# SensorsTeam5.net
KiCad netlist of a schematic drawn in Altium Designer
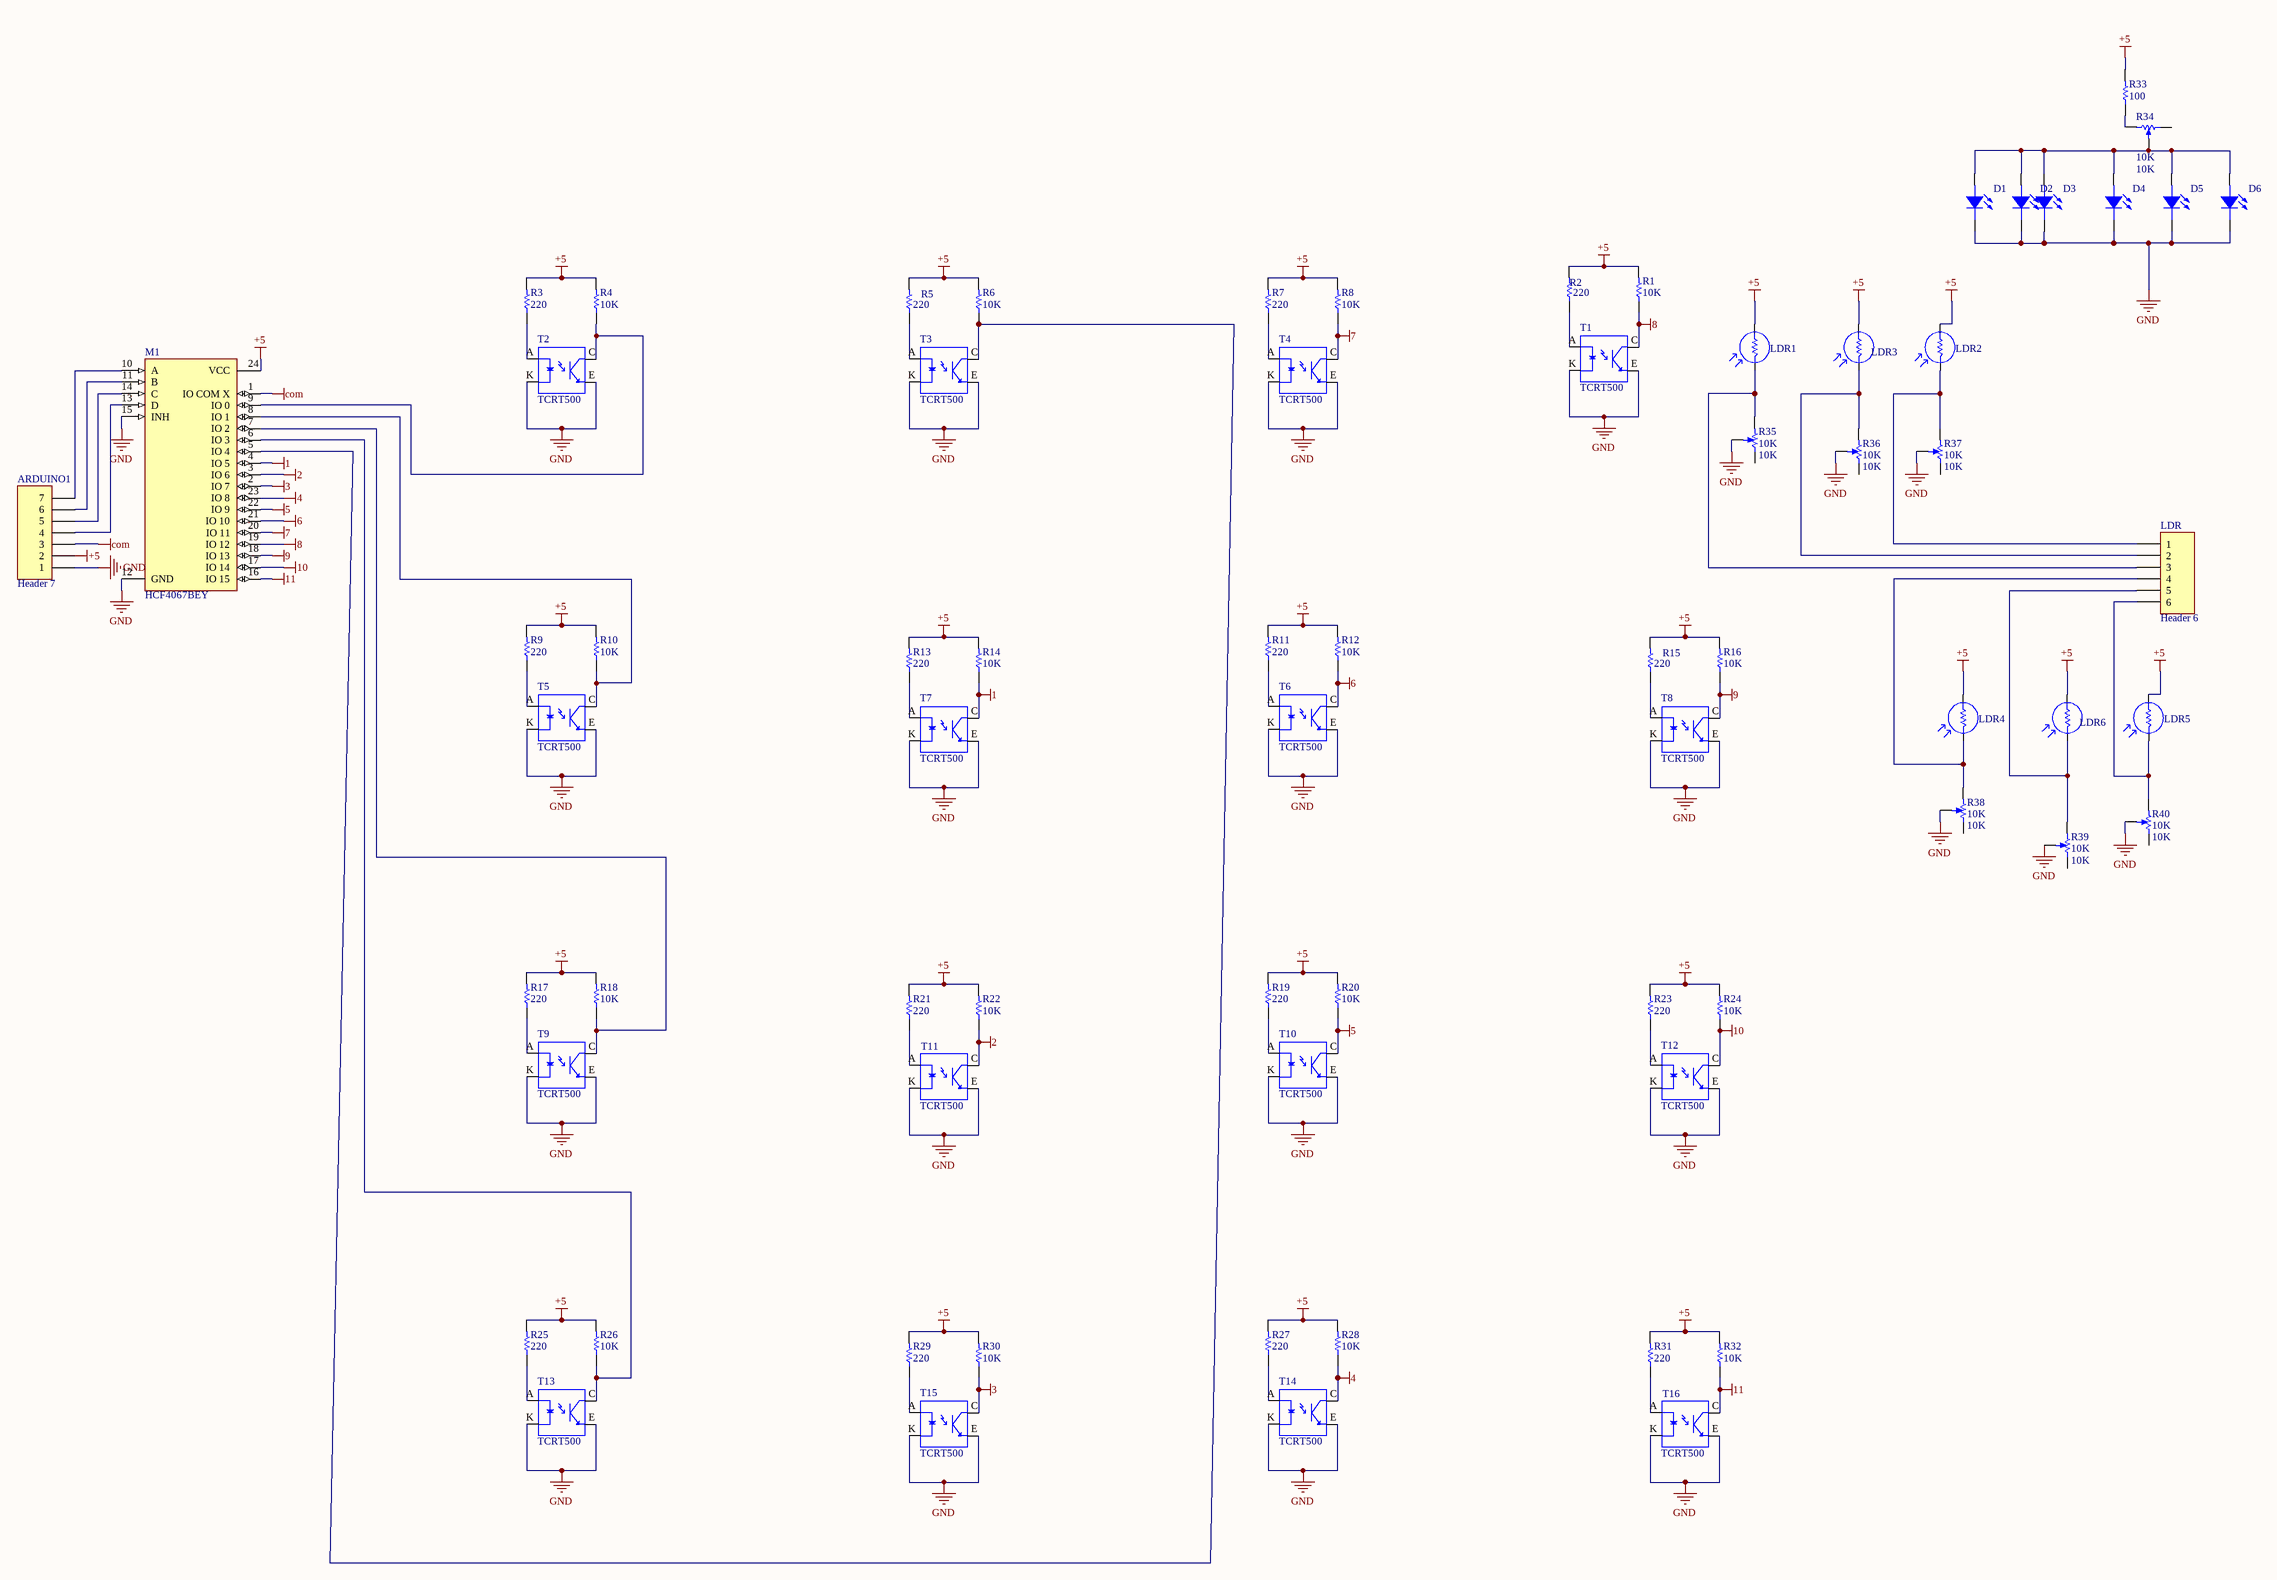
[diagram p0: SensorsTeam5.SchDoc]

(export (version "E")
  (design (tool "Eeschema 10.0.6"))
  (components
    (comp (ref "ARDUINO1")
      (value "Header 7")
      (footprint "HDR1X7")
      (description "Header, 7-Pin")
      (fields (field (name "PUBLISHER") "Altium Limited"))
      (libsource (lib "Altium") (part "Header 7"))
    )
    (comp (ref "D1")
      (value "LED3MM")
      (footprint "LED3mm_GRN")
      (description "Light Emitting Diode")
      (fields (field (name "DESIGNER") "Ali Hafizi"))
      (libsource (lib "Altium") (part "LED 3MM"))
    )
    (comp (ref "D2")
      (value "LED3MM")
      (footprint "LED3mm_GRN")
      (description "Light Emitting Diode")
      (fields (field (name "DESIGNER") "Ali Hafizi"))
      (libsource (lib "Altium") (part "LED 3MM"))
    )
    (comp (ref "D3")
      (value "LED3MM")
      (footprint "LED3mm_GRN")
      (description "Light Emitting Diode")
      (fields (field (name "DESIGNER") "Ali Hafizi"))
      (libsource (lib "Altium") (part "LED 3MM"))
    )
    (comp (ref "D4")
      (value "LED3MM")
      (footprint "LED3mm_GRN")
      (description "Light Emitting Diode")
      (fields (field (name "DESIGNER") "Ali Hafizi"))
      (libsource (lib "Altium") (part "LED 3MM"))
    )
    (comp (ref "D5")
      (value "LED3MM")
      (footprint "LED3mm_GRN")
      (description "Light Emitting Diode")
      (fields (field (name "DESIGNER") "Ali Hafizi"))
      (libsource (lib "Altium") (part "LED 3MM"))
    )
    (comp (ref "D6")
      (value "LED3MM")
      (footprint "LED3mm_GRN")
      (description "Light Emitting Diode")
      (fields (field (name "DESIGNER") "Ali Hafizi"))
      (libsource (lib "Altium") (part "LED 3MM"))
    )
    (comp (ref "LDR")
      (value "Header 6")
      (footprint "HDR1X6")
      (description "Header, 6-Pin")
      (fields (field (name "PUBLISHER") "Altium Limited"))
      (libsource (lib "Altium") (part "Header 6"))
    )
    (comp (ref "LDR1")
      (value "PhotoCell")
      (footprint "PhotoCell")
      (description "Photo Cell- Variable Resistor With Light")
      (fields (field (name "DESIGNER") "Saeid Jorablo"))
      (libsource (lib "Altium") (part "LDR"))
    )
    (comp (ref "LDR2")
      (value "PhotoCell")
      (footprint "PhotoCell")
      (description "Photo Cell- Variable Resistor With Light")
      (fields (field (name "DESIGNER") "Saeid Jorablo"))
      (libsource (lib "Altium") (part "LDR"))
    )
    (comp (ref "LDR3")
      (value "PhotoCell")
      (footprint "PhotoCell")
      (description "Photo Cell- Variable Resistor With Light")
      (fields (field (name "DESIGNER") "Saeid Jorablo"))
      (libsource (lib "Altium") (part "LDR"))
    )
    (comp (ref "LDR4")
      (value "PhotoCell")
      (footprint "PhotoCell")
      (description "Photo Cell- Variable Resistor With Light")
      (fields (field (name "DESIGNER") "Saeid Jorablo"))
      (libsource (lib "Altium") (part "LDR"))
    )
    (comp (ref "LDR5")
      (value "PhotoCell")
      (footprint "PhotoCell")
      (description "Photo Cell- Variable Resistor With Light")
      (fields (field (name "DESIGNER") "Saeid Jorablo"))
      (libsource (lib "Altium") (part "LDR"))
    )
    (comp (ref "LDR6")
      (value "PhotoCell")
      (footprint "PhotoCell")
      (description "Photo Cell- Variable Resistor With Light")
      (fields (field (name "DESIGNER") "Saeid Jorablo"))
      (libsource (lib "Altium") (part "LDR"))
    )
    (comp (ref "M1")
      (value "HCF4067BEY")
      (footprint "PDIP24")
      (description "Analog Multiplexer/Demultiplexer")
      (fields (field (name "PUBLISHER") "Altium Limited"))
      (libsource (lib "ST Logic Multiplexer") (part "HCF4067BEY"))
    )
    (comp (ref "R1")
      (value "10K")
      (footprint "RES-(1/4)")
      (description "RES 0805")
      (fields (field (name "DESIGNER") "Abbas Basereh"))
      (libsource (lib "Altium") (part "RES 0805 0.125W"))
    )
    (comp (ref "R2")
      (value "220")
      (footprint "RES-(1/4)")
      (description "RES 0805")
      (fields (field (name "DESIGNER") "Abbas Basereh"))
      (libsource (lib "Altium") (part "RES 0805 0.125W"))
    )
    (comp (ref "R3")
      (value "220")
      (footprint "RES-(1/4)")
      (description "RES 0805")
      (fields (field (name "DESIGNER") "Abbas Basereh"))
      (libsource (lib "Altium") (part "RES 0805 0.125W"))
    )
    (comp (ref "R4")
      (value "10K")
      (footprint "RES-(1/4)")
      (description "RES 0805")
      (fields (field (name "DESIGNER") "Abbas Basereh"))
      (libsource (lib "Altium") (part "RES 0805 0.125W"))
    )
    (comp (ref "R5")
      (value "220")
      (footprint "RES-(1/4)")
      (description "RES 0805")
      (fields (field (name "DESIGNER") "Abbas Basereh"))
      (libsource (lib "Altium") (part "RES 0805 0.125W"))
    )
    (comp (ref "R6")
      (value "10K")
      (footprint "RES-(1/4)")
      (description "RES 0805")
      (fields (field (name "DESIGNER") "Abbas Basereh"))
      (libsource (lib "Altium") (part "RES 0805 0.125W"))
    )
    (comp (ref "R7")
      (value "220")
      (footprint "RES-(1/4)")
      (description "RES 0805")
      (fields (field (name "DESIGNER") "Abbas Basereh"))
      (libsource (lib "Altium") (part "RES 0805 0.125W"))
    )
    (comp (ref "R8")
      (value "10K")
      (footprint "RES-(1/4)")
      (description "RES 0805")
      (fields (field (name "DESIGNER") "Abbas Basereh"))
      (libsource (lib "Altium") (part "RES 0805 0.125W"))
    )
    (comp (ref "R9")
      (value "220")
      (footprint "RES-(1/4)")
      (description "RES 0805")
      (fields (field (name "DESIGNER") "Abbas Basereh"))
      (libsource (lib "Altium") (part "RES 0805 0.125W"))
    )
    (comp (ref "R10")
      (value "10K")
      (footprint "RES-(1/4)")
      (description "RES 0805")
      (fields (field (name "DESIGNER") "Abbas Basereh"))
      (libsource (lib "Altium") (part "RES 0805 0.125W"))
    )
    (comp (ref "R11")
      (value "220")
      (footprint "RES-(1/4)")
      (description "RES 0805")
      (fields (field (name "DESIGNER") "Abbas Basereh"))
      (libsource (lib "Altium") (part "RES 0805 0.125W"))
    )
    (comp (ref "R12")
      (value "10K")
      (footprint "RES-(1/4)")
      (description "RES 0805")
      (fields (field (name "DESIGNER") "Abbas Basereh"))
      (libsource (lib "Altium") (part "RES 0805 0.125W"))
    )
    (comp (ref "R13")
      (value "220")
      (footprint "RES-(1/4)")
      (description "RES 0805")
      (fields (field (name "DESIGNER") "Abbas Basereh"))
      (libsource (lib "Altium") (part "RES 0805 0.125W"))
    )
    (comp (ref "R14")
      (value "10K")
      (footprint "RES-(1/4)")
      (description "RES 0805")
      (fields (field (name "DESIGNER") "Abbas Basereh"))
      (libsource (lib "Altium") (part "RES 0805 0.125W"))
    )
    (comp (ref "R15")
      (value "220")
      (footprint "RES-(1/4)")
      (description "RES 0805")
      (fields (field (name "DESIGNER") "Abbas Basereh"))
      (libsource (lib "Altium") (part "RES 0805 0.125W"))
    )
    (comp (ref "R16")
      (value "10K")
      (footprint "RES-(1/4)")
      (description "RES 0805")
      (fields (field (name "DESIGNER") "Abbas Basereh"))
      (libsource (lib "Altium") (part "RES 0805 0.125W"))
    )
    (comp (ref "R17")
      (value "220")
      (footprint "RES-(1/4)")
      (description "RES 0805")
      (fields (field (name "DESIGNER") "Abbas Basereh"))
      (libsource (lib "Altium") (part "RES 0805 0.125W"))
    )
    (comp (ref "R18")
      (value "10K")
      (footprint "RES-(1/4)")
      (description "RES 0805")
      (fields (field (name "DESIGNER") "Abbas Basereh"))
      (libsource (lib "Altium") (part "RES 0805 0.125W"))
    )
    (comp (ref "R19")
      (value "220")
      (footprint "RES-(1/4)")
      (description "RES 0805")
      (fields (field (name "DESIGNER") "Abbas Basereh"))
      (libsource (lib "Altium") (part "RES 0805 0.125W"))
    )
    (comp (ref "R20")
      (value "10K")
      (footprint "RES-(1/4)")
      (description "RES 0805")
      (fields (field (name "DESIGNER") "Abbas Basereh"))
      (libsource (lib "Altium") (part "RES 0805 0.125W"))
    )
    (comp (ref "R21")
      (value "220")
      (footprint "RES-(1/4)")
      (description "RES 0805")
      (fields (field (name "DESIGNER") "Abbas Basereh"))
      (libsource (lib "Altium") (part "RES 0805 0.125W"))
    )
    (comp (ref "R22")
      (value "10K")
      (footprint "RES-(1/4)")
      (description "RES 0805")
      (fields (field (name "DESIGNER") "Abbas Basereh"))
      (libsource (lib "Altium") (part "RES 0805 0.125W"))
    )
    (comp (ref "R23")
      (value "220")
      (footprint "RES-(1/4)")
      (description "RES 0805")
      (fields (field (name "DESIGNER") "Abbas Basereh"))
      (libsource (lib "Altium") (part "RES 0805 0.125W"))
    )
    (comp (ref "R24")
      (value "10K")
      (footprint "RES-(1/4)")
      (description "RES 0805")
      (fields (field (name "DESIGNER") "Abbas Basereh"))
      (libsource (lib "Altium") (part "RES 0805 0.125W"))
    )
    (comp (ref "R25")
      (value "220")
      (footprint "RES-(1/4)")
      (description "RES 0805")
      (fields (field (name "DESIGNER") "Abbas Basereh"))
      (libsource (lib "Altium") (part "RES 0805 0.125W"))
    )
    (comp (ref "R26")
      (value "10K")
      (footprint "RES-(1/4)")
      (description "RES 0805")
      (fields (field (name "DESIGNER") "Abbas Basereh"))
      (libsource (lib "Altium") (part "RES 0805 0.125W"))
    )
    (comp (ref "R27")
      (value "220")
      (footprint "RES-(1/4)")
      (description "RES 0805")
      (fields (field (name "DESIGNER") "Abbas Basereh"))
      (libsource (lib "Altium") (part "RES 0805 0.125W"))
    )
    (comp (ref "R28")
      (value "10K")
      (footprint "RES-(1/4)")
      (description "RES 0805")
      (fields (field (name "DESIGNER") "Abbas Basereh"))
      (libsource (lib "Altium") (part "RES 0805 0.125W"))
    )
    (comp (ref "R29")
      (value "220")
      (footprint "RES-(1/4)")
      (description "RES 0805")
      (fields (field (name "DESIGNER") "Abbas Basereh"))
      (libsource (lib "Altium") (part "RES 0805 0.125W"))
    )
    (comp (ref "R30")
      (value "10K")
      (footprint "RES-(1/4)")
      (description "RES 0805")
      (fields (field (name "DESIGNER") "Abbas Basereh"))
      (libsource (lib "Altium") (part "RES 0805 0.125W"))
    )
    (comp (ref "R31")
      (value "220")
      (footprint "RES-(1/4)")
      (description "RES 0805")
      (fields (field (name "DESIGNER") "Abbas Basereh"))
      (libsource (lib "Altium") (part "RES 0805 0.125W"))
    )
    (comp (ref "R32")
      (value "10K")
      (footprint "RES-(1/4)")
      (description "RES 0805")
      (fields (field (name "DESIGNER") "Abbas Basereh"))
      (libsource (lib "Altium") (part "RES 0805 0.125W"))
    )
    (comp (ref "R33")
      (value "100")
      (footprint "RESC3413X04N")
      (description "RES 0805")
      (fields (field (name "DESIGNER") "Abbas Basereh"))
      (libsource (lib "Altium") (part "RES 0805 0.125W"))
    )
    (comp (ref "R34")
      (value "10K")
      (footprint "POT4MM-Small Pot")
      (description "Square Trimming Potentiometer")
      (fields (field (name "ALTIUM_VALUE") "10K") (field (name "PUBLISHER") "Altium Limited"))
      (libsource (lib "Altium") (part "POT SMD"))
    )
    (comp (ref "R35")
      (value "10K")
      (footprint "POT4MM-Small Pot")
      (description "Square Trimming Potentiometer")
      (fields (field (name "ALTIUM_VALUE") "10K") (field (name "PUBLISHER") "Altium Limited"))
      (libsource (lib "Altium") (part "POT SMD"))
    )
    (comp (ref "R36")
      (value "10K")
      (footprint "POT4MM-Small Pot")
      (description "Square Trimming Potentiometer")
      (fields (field (name "ALTIUM_VALUE") "10K") (field (name "PUBLISHER") "Altium Limited"))
      (libsource (lib "Altium") (part "POT SMD"))
    )
    (comp (ref "R37")
      (value "10K")
      (footprint "POT4MM-Small Pot")
      (description "Square Trimming Potentiometer")
      (fields (field (name "ALTIUM_VALUE") "10K") (field (name "PUBLISHER") "Altium Limited"))
      (libsource (lib "Altium") (part "POT SMD"))
    )
    (comp (ref "R38")
      (value "10K")
      (footprint "POT4MM-Small Pot")
      (description "Square Trimming Potentiometer")
      (fields (field (name "ALTIUM_VALUE") "10K") (field (name "PUBLISHER") "Altium Limited"))
      (libsource (lib "Altium") (part "POT SMD"))
    )
    (comp (ref "R39")
      (value "10K")
      (footprint "POT4MM-Small Pot")
      (description "Square Trimming Potentiometer")
      (fields (field (name "ALTIUM_VALUE") "10K") (field (name "PUBLISHER") "Altium Limited"))
      (libsource (lib "Altium") (part "POT SMD"))
    )
    (comp (ref "R40")
      (value "10K")
      (footprint "POT4MM-Small Pot")
      (description "Square Trimming Potentiometer")
      (fields (field (name "ALTIUM_VALUE") "10K") (field (name "PUBLISHER") "Altium Limited"))
      (libsource (lib "Altium") (part "POT SMD"))
    )
    (comp (ref "T1") (value "TCRT500") (footprint "TCRT5000") (libsource (lib "Mahmah") (part "TCRT5000")))
    (comp (ref "T2") (value "TCRT500") (footprint "TCRT5000") (libsource (lib "Mahmah") (part "TCRT5000")))
    (comp (ref "T3") (value "TCRT500") (footprint "TCRT5000") (libsource (lib "Mahmah") (part "TCRT5000")))
    (comp (ref "T4") (value "TCRT500") (footprint "TCRT5000") (libsource (lib "Mahmah") (part "TCRT5000")))
    (comp (ref "T5") (value "TCRT500") (footprint "TCRT5000") (libsource (lib "Mahmah") (part "TCRT5000")))
    (comp (ref "T6") (value "TCRT500") (footprint "TCRT5000") (libsource (lib "Mahmah") (part "TCRT5000")))
    (comp (ref "T7") (value "TCRT500") (footprint "TCRT5000") (libsource (lib "Mahmah") (part "TCRT5000")))
    (comp (ref "T8") (value "TCRT500") (footprint "TCRT5000") (libsource (lib "Mahmah") (part "TCRT5000")))
    (comp (ref "T9") (value "TCRT500") (footprint "TCRT5000") (libsource (lib "Mahmah") (part "TCRT5000")))
    (comp (ref "T10") (value "TCRT500") (footprint "TCRT5000") (libsource (lib "Mahmah") (part "TCRT5000")))
    (comp (ref "T11") (value "TCRT500") (footprint "TCRT5000") (libsource (lib "Mahmah") (part "TCRT5000")))
    (comp (ref "T12") (value "TCRT500") (footprint "TCRT5000") (libsource (lib "Mahmah") (part "TCRT5000")))
    (comp (ref "T13") (value "TCRT500") (footprint "TCRT5000") (libsource (lib "Mahmah") (part "TCRT5000")))
    (comp (ref "T14") (value "TCRT500") (footprint "TCRT5000") (libsource (lib "Mahmah") (part "TCRT5000")))
    (comp (ref "T15") (value "TCRT500") (footprint "TCRT5000") (libsource (lib "Mahmah") (part "TCRT5000")))
    (comp (ref "T16") (value "TCRT500") (footprint "TCRT5000") (libsource (lib "Mahmah") (part "TCRT5000")))
  )
  (nets
    (net (code "1") (name "+5") (class "Default")
      (node (ref "ARDUINO1") (pin "2") (pinfunction "2_2") (pintype "passive"))
      (node (ref "LDR1") (pin "2") (pintype "passive"))
      (node (ref "LDR2") (pin "2") (pintype "passive"))
      (node (ref "LDR3") (pin "2") (pintype "passive"))
      (node (ref "LDR4") (pin "2") (pintype "passive"))
      (node (ref "LDR5") (pin "2") (pintype "passive"))
      (node (ref "LDR6") (pin "2") (pintype "passive"))
      (node (ref "M1") (pin "24") (pinfunction "VCC_24") (pintype "power_in"))
      (node (ref "R1") (pin "2") (pinfunction "2_2") (pintype "passive"))
      (node (ref "R10") (pin "2") (pinfunction "2_2") (pintype "passive"))
      (node (ref "R11") (pin "2") (pinfunction "2_2") (pintype "passive"))
      (node (ref "R12") (pin "2") (pinfunction "2_2") (pintype "passive"))
      (node (ref "R13") (pin "2") (pinfunction "2_2") (pintype "passive"))
      (node (ref "R14") (pin "2") (pinfunction "2_2") (pintype "passive"))
      (node (ref "R15") (pin "2") (pinfunction "2_2") (pintype "passive"))
      (node (ref "R16") (pin "2") (pinfunction "2_2") (pintype "passive"))
      (node (ref "R17") (pin "2") (pinfunction "2_2") (pintype "passive"))
      (node (ref "R18") (pin "2") (pinfunction "2_2") (pintype "passive"))
      (node (ref "R19") (pin "2") (pinfunction "2_2") (pintype "passive"))
      (node (ref "R2") (pin "2") (pinfunction "2_2") (pintype "passive"))
      (node (ref "R20") (pin "2") (pinfunction "2_2") (pintype "passive"))
      (node (ref "R21") (pin "2") (pinfunction "2_2") (pintype "passive"))
      (node (ref "R22") (pin "2") (pinfunction "2_2") (pintype "passive"))
      (node (ref "R23") (pin "2") (pinfunction "2_2") (pintype "passive"))
      (node (ref "R24") (pin "2") (pinfunction "2_2") (pintype "passive"))
      (node (ref "R25") (pin "2") (pinfunction "2_2") (pintype "passive"))
      (node (ref "R26") (pin "2") (pinfunction "2_2") (pintype "passive"))
      (node (ref "R27") (pin "2") (pinfunction "2_2") (pintype "passive"))
      (node (ref "R28") (pin "2") (pinfunction "2_2") (pintype "passive"))
      (node (ref "R29") (pin "2") (pinfunction "2_2") (pintype "passive"))
      (node (ref "R3") (pin "2") (pinfunction "2_2") (pintype "passive"))
      (node (ref "R30") (pin "2") (pinfunction "2_2") (pintype "passive"))
      (node (ref "R31") (pin "2") (pinfunction "2_2") (pintype "passive"))
      (node (ref "R32") (pin "2") (pinfunction "2_2") (pintype "passive"))
      (node (ref "R33") (pin "2") (pinfunction "2_2") (pintype "passive"))
      (node (ref "R4") (pin "2") (pinfunction "2_2") (pintype "passive"))
      (node (ref "R5") (pin "2") (pinfunction "2_2") (pintype "passive"))
      (node (ref "R6") (pin "2") (pinfunction "2_2") (pintype "passive"))
      (node (ref "R7") (pin "2") (pinfunction "2_2") (pintype "passive"))
      (node (ref "R8") (pin "2") (pinfunction "2_2") (pintype "passive"))
      (node (ref "R9") (pin "2") (pinfunction "2_2") (pintype "passive"))
    )
    (net (code "2") (name "1") (class "Default")
      (node (ref "M1") (pin "4") (pinfunction "IO_5_4") (pintype "bidirectional"))
      (node (ref "R14") (pin "1") (pinfunction "1_1") (pintype "passive"))
      (node (ref "T7") (pin "C") (pinfunction "C_C") (pintype "passive"))
    )
    (net (code "3") (name "2") (class "Default")
      (node (ref "M1") (pin "3") (pinfunction "IO_6_3") (pintype "bidirectional"))
      (node (ref "R22") (pin "1") (pinfunction "1_1") (pintype "passive"))
      (node (ref "T11") (pin "C") (pinfunction "C_C") (pintype "passive"))
    )
    (net (code "4") (name "3") (class "Default")
      (node (ref "M1") (pin "2") (pinfunction "IO_7_2") (pintype "bidirectional"))
      (node (ref "R30") (pin "1") (pinfunction "1_1") (pintype "passive"))
      (node (ref "T15") (pin "C") (pinfunction "C_C") (pintype "passive"))
    )
    (net (code "5") (name "4") (class "Default")
      (node (ref "M1") (pin "23") (pinfunction "IO_8_23") (pintype "bidirectional"))
      (node (ref "R28") (pin "1") (pinfunction "1_1") (pintype "passive"))
      (node (ref "T14") (pin "C") (pinfunction "C_C") (pintype "passive"))
    )
    (net (code "6") (name "5") (class "Default")
      (node (ref "M1") (pin "22") (pinfunction "IO_9_22") (pintype "bidirectional"))
      (node (ref "R20") (pin "1") (pinfunction "1_1") (pintype "passive"))
      (node (ref "T10") (pin "C") (pinfunction "C_C") (pintype "passive"))
    )
    (net (code "7") (name "6") (class "Default")
      (node (ref "M1") (pin "21") (pinfunction "IO_10_21") (pintype "bidirectional"))
      (node (ref "R12") (pin "1") (pinfunction "1_1") (pintype "passive"))
      (node (ref "T6") (pin "C") (pinfunction "C_C") (pintype "passive"))
    )
    (net (code "8") (name "7") (class "Default")
      (node (ref "M1") (pin "20") (pinfunction "IO_11_20") (pintype "bidirectional"))
      (node (ref "R8") (pin "1") (pinfunction "1_1") (pintype "passive"))
      (node (ref "T4") (pin "C") (pinfunction "C_C") (pintype "passive"))
    )
    (net (code "9") (name "8") (class "Default")
      (node (ref "M1") (pin "19") (pinfunction "IO_12_19") (pintype "bidirectional"))
      (node (ref "R1") (pin "1") (pinfunction "1_1") (pintype "passive"))
      (node (ref "T1") (pin "C") (pinfunction "C_C") (pintype "passive"))
    )
    (net (code "10") (name "9") (class "Default")
      (node (ref "M1") (pin "18") (pinfunction "IO_13_18") (pintype "bidirectional"))
      (node (ref "R16") (pin "1") (pinfunction "1_1") (pintype "passive"))
      (node (ref "T8") (pin "C") (pinfunction "C_C") (pintype "passive"))
    )
    (net (code "11") (name "10") (class "Default")
      (node (ref "M1") (pin "17") (pinfunction "IO_14_17") (pintype "bidirectional"))
      (node (ref "R24") (pin "1") (pinfunction "1_1") (pintype "passive"))
      (node (ref "T12") (pin "C") (pinfunction "C_C") (pintype "passive"))
    )
    (net (code "12") (name "11") (class "Default")
      (node (ref "M1") (pin "16") (pinfunction "IO_15_16") (pintype "bidirectional"))
      (node (ref "R32") (pin "1") (pinfunction "1_1") (pintype "passive"))
      (node (ref "T16") (pin "C") (pinfunction "C_C") (pintype "passive"))
    )
    (net (code "13") (name "GND") (class "Default")
      (node (ref "ARDUINO1") (pin "1") (pinfunction "1_1") (pintype "passive"))
      (node (ref "D1") (pin "2") (pinfunction "CATHODE_2") (pintype "passive"))
      (node (ref "D2") (pin "2") (pinfunction "CATHODE_2") (pintype "passive"))
      (node (ref "D3") (pin "2") (pinfunction "CATHODE_2") (pintype "passive"))
      (node (ref "D4") (pin "2") (pinfunction "CATHODE_2") (pintype "passive"))
      (node (ref "D5") (pin "2") (pinfunction "CATHODE_2") (pintype "passive"))
      (node (ref "D6") (pin "2") (pinfunction "CATHODE_2") (pintype "passive"))
      (node (ref "M1") (pin "12") (pinfunction "GND_12") (pintype "power_in"))
      (node (ref "M1") (pin "15") (pinfunction "INH_15") (pintype "input"))
      (node (ref "R35") (pin "W") (pinfunction "W_W") (pintype "passive"))
      (node (ref "R36") (pin "W") (pinfunction "W_W") (pintype "passive"))
      (node (ref "R37") (pin "W") (pinfunction "W_W") (pintype "passive"))
      (node (ref "R38") (pin "W") (pinfunction "W_W") (pintype "passive"))
      (node (ref "R39") (pin "W") (pinfunction "W_W") (pintype "passive"))
      (node (ref "R40") (pin "W") (pinfunction "W_W") (pintype "passive"))
      (node (ref "T1") (pin "E") (pinfunction "E_E") (pintype "passive"))
      (node (ref "T1") (pin "K") (pinfunction "K_K") (pintype "passive"))
      (node (ref "T10") (pin "E") (pinfunction "E_E") (pintype "passive"))
      (node (ref "T10") (pin "K") (pinfunction "K_K") (pintype "passive"))
      (node (ref "T11") (pin "E") (pinfunction "E_E") (pintype "passive"))
      (node (ref "T11") (pin "K") (pinfunction "K_K") (pintype "passive"))
      (node (ref "T12") (pin "E") (pinfunction "E_E") (pintype "passive"))
      (node (ref "T12") (pin "K") (pinfunction "K_K") (pintype "passive"))
      (node (ref "T13") (pin "E") (pinfunction "E_E") (pintype "passive"))
      (node (ref "T13") (pin "K") (pinfunction "K_K") (pintype "passive"))
      (node (ref "T14") (pin "E") (pinfunction "E_E") (pintype "passive"))
      (node (ref "T14") (pin "K") (pinfunction "K_K") (pintype "passive"))
      (node (ref "T15") (pin "E") (pinfunction "E_E") (pintype "passive"))
      (node (ref "T15") (pin "K") (pinfunction "K_K") (pintype "passive"))
      (node (ref "T16") (pin "E") (pinfunction "E_E") (pintype "passive"))
      (node (ref "T16") (pin "K") (pinfunction "K_K") (pintype "passive"))
      (node (ref "T2") (pin "E") (pinfunction "E_E") (pintype "passive"))
      (node (ref "T2") (pin "K") (pinfunction "K_K") (pintype "passive"))
      (node (ref "T3") (pin "E") (pinfunction "E_E") (pintype "passive"))
      (node (ref "T3") (pin "K") (pinfunction "K_K") (pintype "passive"))
      (node (ref "T4") (pin "E") (pinfunction "E_E") (pintype "passive"))
      (node (ref "T4") (pin "K") (pinfunction "K_K") (pintype "passive"))
      (node (ref "T5") (pin "E") (pinfunction "E_E") (pintype "passive"))
      (node (ref "T5") (pin "K") (pinfunction "K_K") (pintype "passive"))
      (node (ref "T6") (pin "E") (pinfunction "E_E") (pintype "passive"))
      (node (ref "T6") (pin "K") (pinfunction "K_K") (pintype "passive"))
      (node (ref "T7") (pin "E") (pinfunction "E_E") (pintype "passive"))
      (node (ref "T7") (pin "K") (pinfunction "K_K") (pintype "passive"))
      (node (ref "T8") (pin "E") (pinfunction "E_E") (pintype "passive"))
      (node (ref "T8") (pin "K") (pinfunction "K_K") (pintype "passive"))
      (node (ref "T9") (pin "E") (pinfunction "E_E") (pintype "passive"))
      (node (ref "T9") (pin "K") (pinfunction "K_K") (pintype "passive"))
    )
    (net (code "14") (name "Net-(D1-ANODE)") (class "Default")
      (node (ref "D1") (pin "1") (pinfunction "ANODE_1") (pintype "passive"))
      (node (ref "D2") (pin "1") (pinfunction "ANODE_1") (pintype "passive"))
      (node (ref "D3") (pin "1") (pinfunction "ANODE_1") (pintype "passive"))
      (node (ref "D4") (pin "1") (pinfunction "ANODE_1") (pintype "passive"))
      (node (ref "D5") (pin "1") (pinfunction "ANODE_1") (pintype "passive"))
      (node (ref "D6") (pin "1") (pinfunction "ANODE_1") (pintype "passive"))
      (node (ref "R34") (pin "W") (pinfunction "W_W") (pintype "passive"))
    )
    (net (code "15") (name "Net-(M1-A)") (class "Default")
      (node (ref "ARDUINO1") (pin "7") (pinfunction "7_7") (pintype "passive"))
      (node (ref "M1") (pin "10") (pinfunction "A_10") (pintype "input"))
    )
    (net (code "16") (name "Net-(M1-B)") (class "Default")
      (node (ref "ARDUINO1") (pin "6") (pinfunction "6_6") (pintype "passive"))
      (node (ref "M1") (pin "11") (pinfunction "B_11") (pintype "input"))
    )
    (net (code "17") (name "Net-(M1-C)") (class "Default")
      (node (ref "ARDUINO1") (pin "5") (pinfunction "5_5") (pintype "passive"))
      (node (ref "M1") (pin "14") (pinfunction "C_14") (pintype "input"))
    )
    (net (code "18") (name "Net-(M1-D)") (class "Default")
      (node (ref "ARDUINO1") (pin "4") (pinfunction "4_4") (pintype "passive"))
      (node (ref "M1") (pin "13") (pinfunction "D_13") (pintype "input"))
    )
    (net (code "19") (name "Net-(M1-IO_0)") (class "Default")
      (node (ref "M1") (pin "9") (pinfunction "IO_0_9") (pintype "bidirectional"))
      (node (ref "R4") (pin "1") (pinfunction "1_1") (pintype "passive"))
      (node (ref "T2") (pin "C") (pinfunction "C_C") (pintype "passive"))
    )
    (net (code "20") (name "Net-(M1-IO_1)") (class "Default")
      (node (ref "M1") (pin "8") (pinfunction "IO_1_8") (pintype "bidirectional"))
      (node (ref "R10") (pin "1") (pinfunction "1_1") (pintype "passive"))
      (node (ref "T5") (pin "C") (pinfunction "C_C") (pintype "passive"))
    )
    (net (code "21") (name "Net-(M1-IO_2)") (class "Default")
      (node (ref "M1") (pin "7") (pinfunction "IO_2_7") (pintype "bidirectional"))
      (node (ref "R18") (pin "1") (pinfunction "1_1") (pintype "passive"))
      (node (ref "T9") (pin "C") (pinfunction "C_C") (pintype "passive"))
    )
    (net (code "22") (name "Net-(M1-IO_3)") (class "Default")
      (node (ref "M1") (pin "6") (pinfunction "IO_3_6") (pintype "bidirectional"))
      (node (ref "R26") (pin "1") (pinfunction "1_1") (pintype "passive"))
      (node (ref "T13") (pin "C") (pinfunction "C_C") (pintype "passive"))
    )
    (net (code "23") (name "Net-(M1-IO_4)") (class "Default")
      (node (ref "M1") (pin "5") (pinfunction "IO_4_5") (pintype "bidirectional"))
      (node (ref "R6") (pin "1") (pinfunction "1_1") (pintype "passive"))
      (node (ref "T3") (pin "C") (pinfunction "C_C") (pintype "passive"))
    )
    (net (code "24") (name "Net-(R2-Pad1)") (class "Default")
      (node (ref "R2") (pin "1") (pinfunction "1_1") (pintype "passive"))
      (node (ref "T1") (pin "A") (pinfunction "A_A") (pintype "passive"))
    )
    (net (code "25") (name "Net-(R3-Pad1)") (class "Default")
      (node (ref "R3") (pin "1") (pinfunction "1_1") (pintype "passive"))
      (node (ref "T2") (pin "A") (pinfunction "A_A") (pintype "passive"))
    )
    (net (code "26") (name "Net-(R5-Pad1)") (class "Default")
      (node (ref "R5") (pin "1") (pinfunction "1_1") (pintype "passive"))
      (node (ref "T3") (pin "A") (pinfunction "A_A") (pintype "passive"))
    )
    (net (code "27") (name "Net-(R7-Pad1)") (class "Default")
      (node (ref "R7") (pin "1") (pinfunction "1_1") (pintype "passive"))
      (node (ref "T4") (pin "A") (pinfunction "A_A") (pintype "passive"))
    )
    (net (code "28") (name "Net-(R9-Pad1)") (class "Default")
      (node (ref "R9") (pin "1") (pinfunction "1_1") (pintype "passive"))
      (node (ref "T5") (pin "A") (pinfunction "A_A") (pintype "passive"))
    )
    (net (code "29") (name "Net-(R11-Pad1)") (class "Default")
      (node (ref "R11") (pin "1") (pinfunction "1_1") (pintype "passive"))
      (node (ref "T6") (pin "A") (pinfunction "A_A") (pintype "passive"))
    )
    (net (code "30") (name "Net-(R13-Pad1)") (class "Default")
      (node (ref "R13") (pin "1") (pinfunction "1_1") (pintype "passive"))
      (node (ref "T7") (pin "A") (pinfunction "A_A") (pintype "passive"))
    )
    (net (code "31") (name "Net-(R15-Pad1)") (class "Default")
      (node (ref "R15") (pin "1") (pinfunction "1_1") (pintype "passive"))
      (node (ref "T8") (pin "A") (pinfunction "A_A") (pintype "passive"))
    )
    (net (code "32") (name "Net-(R17-Pad1)") (class "Default")
      (node (ref "R17") (pin "1") (pinfunction "1_1") (pintype "passive"))
      (node (ref "T9") (pin "A") (pinfunction "A_A") (pintype "passive"))
    )
    (net (code "33") (name "Net-(R19-Pad1)") (class "Default")
      (node (ref "R19") (pin "1") (pinfunction "1_1") (pintype "passive"))
      (node (ref "T10") (pin "A") (pinfunction "A_A") (pintype "passive"))
    )
    (net (code "34") (name "Net-(R21-Pad1)") (class "Default")
      (node (ref "R21") (pin "1") (pinfunction "1_1") (pintype "passive"))
      (node (ref "T11") (pin "A") (pinfunction "A_A") (pintype "passive"))
    )
    (net (code "35") (name "Net-(R23-Pad1)") (class "Default")
      (node (ref "R23") (pin "1") (pinfunction "1_1") (pintype "passive"))
      (node (ref "T12") (pin "A") (pinfunction "A_A") (pintype "passive"))
    )
    (net (code "36") (name "Net-(R25-Pad1)") (class "Default")
      (node (ref "R25") (pin "1") (pinfunction "1_1") (pintype "passive"))
      (node (ref "T13") (pin "A") (pinfunction "A_A") (pintype "passive"))
    )
    (net (code "37") (name "Net-(R27-Pad1)") (class "Default")
      (node (ref "R27") (pin "1") (pinfunction "1_1") (pintype "passive"))
      (node (ref "T14") (pin "A") (pinfunction "A_A") (pintype "passive"))
    )
    (net (code "38") (name "Net-(R29-Pad1)") (class "Default")
      (node (ref "R29") (pin "1") (pinfunction "1_1") (pintype "passive"))
      (node (ref "T15") (pin "A") (pinfunction "A_A") (pintype "passive"))
    )
    (net (code "39") (name "Net-(R31-Pad1)") (class "Default")
      (node (ref "R31") (pin "1") (pinfunction "1_1") (pintype "passive"))
      (node (ref "T16") (pin "A") (pinfunction "A_A") (pintype "passive"))
    )
    (net (code "40") (name "Net-(R34--)") (class "Default")
      (node (ref "R33") (pin "1") (pinfunction "1_1") (pintype "passive"))
      (node (ref "R34") (pin "CCW") (pinfunction "-_CCW") (pintype "passive"))
    )
    (net (code "41") (name "Net-(R35--)") (class "Default")
      (node (ref "LDR") (pin "3") (pinfunction "3_3") (pintype "passive"))
      (node (ref "LDR1") (pin "1") (pintype "passive"))
      (node (ref "R35") (pin "CCW") (pinfunction "-_CCW") (pintype "passive"))
    )
    (net (code "42") (name "Net-(R36--)") (class "Default")
      (node (ref "LDR") (pin "2") (pinfunction "2_2") (pintype "passive"))
      (node (ref "LDR3") (pin "1") (pintype "passive"))
      (node (ref "R36") (pin "CCW") (pinfunction "-_CCW") (pintype "passive"))
    )
    (net (code "43") (name "Net-(R37--)") (class "Default")
      (node (ref "LDR") (pin "1") (pinfunction "1_1") (pintype "passive"))
      (node (ref "LDR2") (pin "1") (pintype "passive"))
      (node (ref "R37") (pin "CCW") (pinfunction "-_CCW") (pintype "passive"))
    )
    (net (code "44") (name "Net-(R38--)") (class "Default")
      (node (ref "LDR") (pin "4") (pinfunction "4_4") (pintype "passive"))
      (node (ref "LDR4") (pin "1") (pintype "passive"))
      (node (ref "R38") (pin "CCW") (pinfunction "-_CCW") (pintype "passive"))
    )
    (net (code "45") (name "Net-(R39--)") (class "Default")
      (node (ref "LDR") (pin "5") (pinfunction "5_5") (pintype "passive"))
      (node (ref "LDR6") (pin "1") (pintype "passive"))
      (node (ref "R39") (pin "CCW") (pinfunction "-_CCW") (pintype "passive"))
    )
    (net (code "46") (name "Net-(R40--)") (class "Default")
      (node (ref "LDR") (pin "6") (pinfunction "6_6") (pintype "passive"))
      (node (ref "LDR5") (pin "1") (pintype "passive"))
      (node (ref "R40") (pin "CCW") (pinfunction "-_CCW") (pintype "passive"))
    )
    (net (code "47") (name "com") (class "Default")
      (node (ref "ARDUINO1") (pin "3") (pinfunction "3_3") (pintype "passive"))
      (node (ref "M1") (pin "1") (pinfunction "IO_COM_X_1") (pintype "bidirectional"))
    )
    (net (code "48") (name "unconnected-(R34-+-PadCW)") (class "Default")
      (node (ref "R34") (pin "CW") (pinfunction "+_CW") (pintype "passive"))
    )
    (net (code "49") (name "unconnected-(R35-+-PadCW)") (class "Default")
      (node (ref "R35") (pin "CW") (pinfunction "+_CW") (pintype "passive"))
    )
    (net (code "50") (name "unconnected-(R36-+-PadCW)") (class "Default")
      (node (ref "R36") (pin "CW") (pinfunction "+_CW") (pintype "passive"))
    )
    (net (code "51") (name "unconnected-(R37-+-PadCW)") (class "Default")
      (node (ref "R37") (pin "CW") (pinfunction "+_CW") (pintype "passive"))
    )
    (net (code "52") (name "unconnected-(R38-+-PadCW)") (class "Default")
      (node (ref "R38") (pin "CW") (pinfunction "+_CW") (pintype "passive"))
    )
    (net (code "53") (name "unconnected-(R39-+-PadCW)") (class "Default")
      (node (ref "R39") (pin "CW") (pinfunction "+_CW") (pintype "passive"))
    )
    (net (code "54") (name "unconnected-(R40-+-PadCW)") (class "Default")
      (node (ref "R40") (pin "CW") (pinfunction "+_CW") (pintype "passive"))
    )
  )
)
